# SD_Card_Socket.net
KiCad netlist of a schematic drawn in Altium Designer
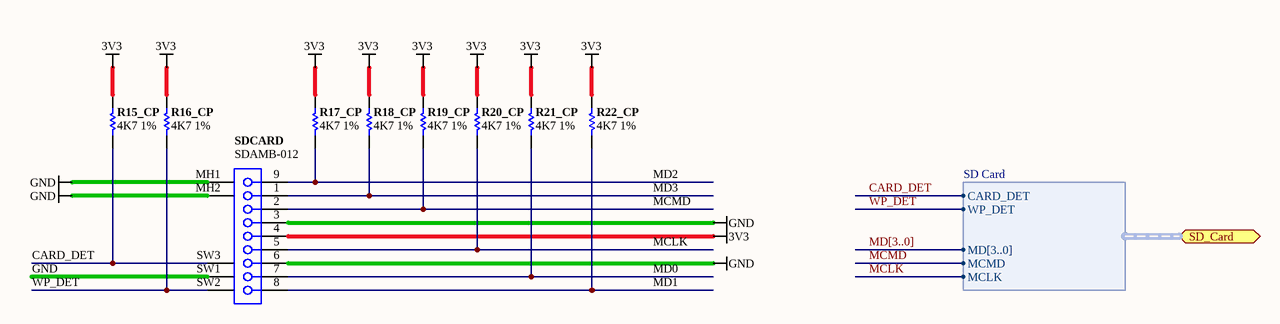
[diagram p0: SD_Card_Socket.SchDoc]

(export (version "E")
  (design (tool "Eeschema 10.0.6"))
  (components
    (comp (ref "R15_CP")
      (value "4K7 1%")
      (footprint "RESC1005-STAR")
      (description "Resistor, 4K7 1% 0402 (1005)")
      (fields (field (name "TOLERANCE") "1 %"))
      (libsource (lib "AltiumDesignLibrary") (part "RES"))
    )
    (comp (ref "R16_CP")
      (value "4K7 1%")
      (footprint "RESC1005-STAR")
      (description "Resistor, 4K7 1% 0402 (1005)")
      (fields (field (name "TOLERANCE") "1 %"))
      (libsource (lib "AltiumDesignLibrary") (part "RES"))
    )
    (comp (ref "R17_CP")
      (value "4K7 1%")
      (footprint "RESC1005-STAR")
      (description "Resistor, 4K7 1% 0402 (1005)")
      (fields (field (name "TOLERANCE") "1 %"))
      (libsource (lib "AltiumDesignLibrary") (part "RES"))
    )
    (comp (ref "R18_CP")
      (value "4K7 1%")
      (footprint "RESC1005-STAR")
      (description "Resistor, 4K7 1% 0402 (1005)")
      (fields (field (name "TOLERANCE") "1 %"))
      (libsource (lib "AltiumDesignLibrary") (part "RES"))
    )
    (comp (ref "R19_CP")
      (value "4K7 1%")
      (footprint "RESC1005-STAR")
      (description "Resistor, 4K7 1% 0402 (1005)")
      (fields (field (name "TOLERANCE") "1 %"))
      (libsource (lib "AltiumDesignLibrary") (part "RES"))
    )
    (comp (ref "R20_CP")
      (value "4K7 1%")
      (footprint "RESC1005-STAR")
      (description "Resistor, 4K7 1% 0402 (1005)")
      (fields (field (name "TOLERANCE") "1 %"))
      (libsource (lib "AltiumDesignLibrary") (part "RES"))
    )
    (comp (ref "R21_CP")
      (value "4K7 1%")
      (footprint "RESC1005-STAR")
      (description "Resistor, 4K7 1% 0402 (1005)")
      (fields (field (name "TOLERANCE") "1 %"))
      (libsource (lib "AltiumDesignLibrary") (part "RES"))
    )
    (comp (ref "R22_CP")
      (value "4K7 1%")
      (footprint "RESC1005-STAR")
      (description "Resistor, 4K7 1% 0402 (1005)")
      (fields (field (name "TOLERANCE") "1 %"))
      (libsource (lib "AltiumDesignLibrary") (part "RES"))
    )
    (comp (ref "SDCARD")
      (value "SDAMB-012")
      (footprint "SDAMB-012")
      (description "SDCARD Connector SDAMB-012")
      (libsource (lib "AltiumDesignLibrary") (part "SDAMB-012"))
    )
  )
  (nets
    (net (code "3") (name "/CARD_DET") (class "Default")
      (node (ref "R15_CP") (pin "1") (pinfunction "1_1") (pintype "passive"))
      (node (ref "SDCARD") (pin "SW3") (pinfunction "SW3_SW3") (pintype "passive"))
    )
    (net (code "4") (name "/MCLK") (class "Default")
      (node (ref "R20_CP") (pin "1") (pinfunction "1_1") (pintype "passive"))
      (node (ref "SDCARD") (pin "5") (pinfunction "5_5") (pintype "passive"))
    )
    (net (code "5") (name "/MCMD") (class "Default")
      (node (ref "R19_CP") (pin "1") (pinfunction "1_1") (pintype "passive"))
      (node (ref "SDCARD") (pin "2") (pinfunction "2_2") (pintype "passive"))
    )
    (net (code "6") (name "/MD0") (class "Default")
      (node (ref "R21_CP") (pin "1") (pinfunction "1_1") (pintype "passive"))
      (node (ref "SDCARD") (pin "7") (pinfunction "7_7") (pintype "passive"))
    )
    (net (code "7") (name "/MD1") (class "Default")
      (node (ref "R22_CP") (pin "1") (pinfunction "1_1") (pintype "passive"))
      (node (ref "SDCARD") (pin "8") (pinfunction "8_8") (pintype "passive"))
    )
    (net (code "8") (name "/MD2") (class "Default")
      (node (ref "R17_CP") (pin "1") (pinfunction "1_1") (pintype "passive"))
      (node (ref "SDCARD") (pin "9") (pinfunction "9_9") (pintype "passive"))
    )
    (net (code "9") (name "/MD3") (class "Default")
      (node (ref "R18_CP") (pin "1") (pinfunction "1_1") (pintype "passive"))
      (node (ref "SDCARD") (pin "1") (pinfunction "1_1") (pintype "passive"))
    )
    (net (code "11") (name "/WP_DET") (class "Default")
      (node (ref "R16_CP") (pin "1") (pinfunction "1_1") (pintype "passive"))
      (node (ref "SDCARD") (pin "SW2") (pinfunction "SW2_SW2") (pintype "passive"))
    )
    (net (code "13") (name "3V3") (class "Default")
      (node (ref "R15_CP") (pin "2") (pinfunction "2_2") (pintype "passive"))
      (node (ref "R16_CP") (pin "2") (pinfunction "2_2") (pintype "passive"))
      (node (ref "R17_CP") (pin "2") (pinfunction "2_2") (pintype "passive"))
      (node (ref "R18_CP") (pin "2") (pinfunction "2_2") (pintype "passive"))
      (node (ref "R19_CP") (pin "2") (pinfunction "2_2") (pintype "passive"))
      (node (ref "R20_CP") (pin "2") (pinfunction "2_2") (pintype "passive"))
      (node (ref "R21_CP") (pin "2") (pinfunction "2_2") (pintype "passive"))
      (node (ref "R22_CP") (pin "2") (pinfunction "2_2") (pintype "passive"))
      (node (ref "SDCARD") (pin "4") (pinfunction "4_4") (pintype "passive"))
    )
    (net (code "14") (name "GND") (class "Default")
      (node (ref "SDCARD") (pin "3") (pinfunction "3_3") (pintype "passive"))
      (node (ref "SDCARD") (pin "6") (pinfunction "6_6") (pintype "passive"))
      (node (ref "SDCARD") (pin "MH1") (pinfunction "MH1_MH1") (pintype "passive"))
      (node (ref "SDCARD") (pin "MH2") (pinfunction "MH2_MH2") (pintype "passive"))
      (node (ref "SDCARD") (pin "SW1") (pinfunction "SW1_SW1") (pintype "passive"))
    )
  )
)
